# PSU.net
KiCad netlist of a schematic drawn in Altium Designer
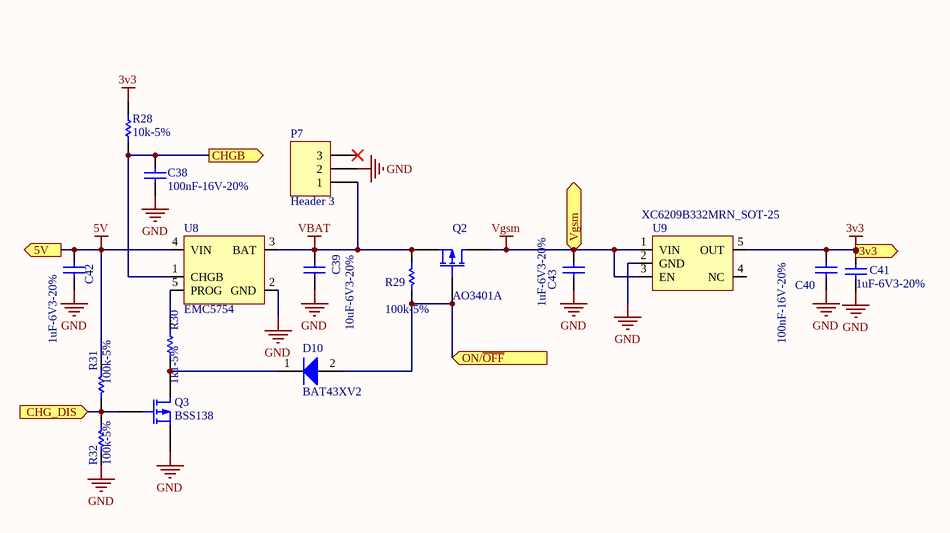
[diagram p0: PSU.SchDoc]

(export (version "E")
  (design (tool "Eeschema 10.0.6"))
  (components
    (comp (ref "C38")
      (value "100nF-16V-20%")
      (footprint "C0402")
      (description "CAP CER 0.1UF 16V Y5V 0402")
      (fields
        (field (name "MANUFACTURER") "Yageo")
        (field (name "DIGI-KEY PART NUMBER") "311-1047-1-ND")
        (field (name "PUBLISHER") "Altium Limited")
      )
      (libsource (lib "Miscellaneous Devices") (part "Cap"))
    )
    (comp (ref "C39")
      (value "10uF-6V3-20%")
      (footprint "C0402")
      (description "CAP CER 10UF 6.3V 20% X5R 0603")
      (fields
        (field (name "MANUFACTURER") "Yageo")
        (field (name "DIGI-KEY PART NUMBER") "311-1448-1-ND")
        (field (name "PUBLISHER") "Altium Limited")
      )
      (libsource (lib "Miscellaneous Devices") (part "Cap"))
    )
    (comp (ref "C40")
      (value "100nF-16V-20%")
      (footprint "C0402")
      (description "CAP CER 0.1UF 16V Y5V 0402")
      (fields
        (field (name "MANUFACTURER") "Yageo")
        (field (name "DIGI-KEY PART NUMBER") "311-1047-1-ND")
        (field (name "PUBLISHER") "Altium Limited")
      )
      (libsource (lib "Miscellaneous Devices") (part "Cap"))
    )
    (comp (ref "C41")
      (value "1uF-6V3-20%")
      (footprint "C0402")
      (description "CAP CER 1UF 6.3V Y5V 0402")
      (fields
        (field (name "MANUFACTURER") "Yageo")
        (field (name "DIGI-KEY PART NUMBER") "311-1377-2-ND")
        (field (name "PUBLISHER") "Altium Limited")
      )
      (libsource (lib "Miscellaneous Devices") (part "Cap"))
    )
    (comp (ref "C42")
      (value "1uF-6V3-20%")
      (footprint "C0402")
      (description "CAP CER 1UF 6.3V Y5V 0402")
      (fields
        (field (name "MANUFACTURER") "Yageo")
        (field (name "DIGI-KEY PART NUMBER") "311-1377-2-ND")
        (field (name "PUBLISHER") "Altium Limited")
      )
      (libsource (lib "Miscellaneous Devices") (part "Cap"))
    )
    (comp (ref "C43")
      (value "1uF-6V3-20%")
      (footprint "C0402")
      (description "CAP CER 1UF 6.3V Y5V 0402")
      (fields
        (field (name "MANUFACTURER") "Yageo")
        (field (name "DIGI-KEY PART NUMBER") "311-1377-2-ND")
        (field (name "PUBLISHER") "Altium Limited")
      )
      (libsource (lib "Miscellaneous Devices") (part "Cap"))
    )
    (comp (ref "D10")
      (value "BAT43XV2")
      (footprint "SOD-523F")
      (description "Diode Type SMD")
      (fields
        (field (name "DIGI-KEY PART NUMBER") "BAT43XV2CT-ND")
        (field (name "MANUFACTURER") "Fairchild Semiconductor")
        (field (name "PUBLISHER") "Altium Limited")
      )
      (libsource (lib "Miscellaneous Devices") (part "Diode"))
    )
    (comp (ref "P7")
      (value "Header 3")
      (footprint "BAT_CON")
      (description "Header, 3-Pin")
      (fields (field (name "PUBLISHER") "Altium Limited"))
      (libsource (lib "Miscellaneous Connectors") (part "Header 3"))
    )
    (comp (ref "Q2")
      (value "AO3401A")
      (footprint "SOT23-3")
      (description "MOSFET P-CH -30V -4.3A SOT23")
      (fields
        (field (name "DIGI-KEY PART NUMBER") "785-1001-1-ND")
        (field (name "MANUFACTURER") "Alpha & Omega Semiconductor Inc")
        (field (name "PUBLISHER") "Altium Limited")
      )
      (libsource (lib "") (part "MOSFET-P_1"))
    )
    (comp (ref "Q3")
      (value "BSS138")
      (footprint "SOT23-3")
      (description "MOSFET N-CH 50V 200MA SOT23-3")
      (fields
        (field (name "DIGI-KEY PART NUMBER") "BSS138-FDICT-ND")
        (field (name "MANUFACTURER") "Diodes Inc")
        (field (name "PUBLISHER") "Altium Limited")
      )
      (libsource (lib "Miscellaneous Devices") (part "MOSFET-P"))
    )
    (comp (ref "R28")
      (value "10k-5%")
      (footprint "R0402")
      (description "RES 10K OHM 1/16W 5% 0402 SMD")
      (fields
        (field (name "DIGI-KEY PART NUMBER") "311-10KJRCT-ND")
        (field (name "MANUFACTURER") "Yageo")
        (field (name "PUBLISHER") "Altium Limited")
      )
      (libsource (lib "Miscellaneous Devices") (part "Res1"))
    )
    (comp (ref "R29")
      (value "100k-5%")
      (footprint "R0402")
      (description "RES 100K OHM 1/16W 5% 0402 SMD")
      (fields
        (field (name "DIGI-KEY PART NUMBER") "311-100KJRCT-ND")
        (field (name "MANUFACTURER") "Yageo")
        (field (name "PUBLISHER") "Altium Limited")
      )
      (libsource (lib "Miscellaneous Devices") (part "Res1"))
    )
    (comp (ref "R30")
      (value "1k1-5%")
      (footprint "R0402")
      (description "RES 1.1K OHM 1/16W 5% 0402 SMD")
      (fields
        (field (name "DIGI-KEY PART NUMBER") "311-1.1KJRCT-ND")
        (field (name "MANUFACTURER") "Yageo")
        (field (name "PUBLISHER") "Altium Limited")
      )
      (libsource (lib "Miscellaneous Devices") (part "Res1"))
    )
    (comp (ref "R31")
      (value "100k-5%")
      (footprint "R0402")
      (description "RES 100K OHM 1/16W 5% 0402 SMD")
      (fields
        (field (name "DIGI-KEY PART NUMBER") "311-100KJRCT-ND")
        (field (name "MANUFACTURER") "Yageo")
        (field (name "PUBLISHER") "Altium Limited")
      )
      (libsource (lib "Miscellaneous Devices") (part "Res1"))
    )
    (comp (ref "R32")
      (value "100k-5%")
      (footprint "R0402")
      (description "RES 100K OHM 1/16W 5% 0402 SMD")
      (fields
        (field (name "DIGI-KEY PART NUMBER") "311-100KJRCT-ND")
        (field (name "MANUFACTURER") "Yageo")
        (field (name "PUBLISHER") "Altium Limited")
      )
      (libsource (lib "Miscellaneous Devices") (part "Res1"))
    )
    (comp (ref "U8") (value "EMC5754") (footprint "SOT23-5") (libsource (lib "Lib") (part "EMC5754")))
    (comp (ref "U9")
      (value "XC6209B332MRN_SOT-25")
      (footprint "SOT23-5")
      (fields (field (name "MANUFACTURER") "Tyrone"))
      (libsource (lib "Schlib1") (part "XC6209B332MRN_SOT-25"))
    )
  )
  (nets
    (net (code "2") (name "/CHGB") (class "Default")
      (node (ref "C38") (pin "2") (pinfunction "2_2") (pintype "passive"))
      (node (ref "R28") (pin "1") (pinfunction "1_1") (pintype "passive"))
      (node (ref "U8") (pin "1") (pinfunction "CHGB_1") (pintype "passive"))
    )
    (net (code "3") (name "/CHG_DIS") (class "Default")
      (node (ref "Q3") (pin "1") (pinfunction "G_1") (pintype "passive"))
      (node (ref "R31") (pin "1") (pinfunction "1_1") (pintype "passive"))
      (node (ref "R32") (pin "2") (pinfunction "2_2") (pintype "passive"))
    )
    (net (code "4") (name "/ON{slash}~{OFF}") (class "Default")
      (node (ref "D10") (pin "2") (pinfunction "A_2") (pintype "passive"))
      (node (ref "Q2") (pin "1") (pinfunction "G_1") (pintype "passive"))
      (node (ref "R29") (pin "1") (pinfunction "1_1") (pintype "passive"))
    )
    (net (code "5") (name "3v3") (class "Default")
      (node (ref "C40") (pin "2") (pinfunction "2_2") (pintype "passive"))
      (node (ref "C41") (pin "1") (pinfunction "1_1") (pintype "passive"))
      (node (ref "R28") (pin "2") (pinfunction "2_2") (pintype "passive"))
      (node (ref "U9") (pin "5") (pinfunction "OUT_5") (pintype "passive"))
    )
    (net (code "6") (name "5V") (class "Default")
      (node (ref "C42") (pin "2") (pinfunction "2_2") (pintype "passive"))
      (node (ref "R31") (pin "2") (pinfunction "2_2") (pintype "passive"))
      (node (ref "U8") (pin "4") (pinfunction "VIN_4") (pintype "passive"))
    )
    (net (code "7") (name "GND") (class "Default")
      (node (ref "C38") (pin "1") (pinfunction "1_1") (pintype "passive"))
      (node (ref "C39") (pin "1") (pinfunction "1_1") (pintype "passive"))
      (node (ref "C40") (pin "1") (pinfunction "1_1") (pintype "passive"))
      (node (ref "C41") (pin "2") (pinfunction "2_2") (pintype "passive"))
      (node (ref "C42") (pin "1") (pinfunction "1_1") (pintype "passive"))
      (node (ref "C43") (pin "2") (pinfunction "2_2") (pintype "passive"))
      (node (ref "P7") (pin "2") (pinfunction "2_2") (pintype "passive"))
      (node (ref "Q3") (pin "2") (pinfunction "S_2") (pintype "passive"))
      (node (ref "R32") (pin "1") (pinfunction "1_1") (pintype "passive"))
      (node (ref "U8") (pin "2") (pinfunction "GND_2") (pintype "passive"))
      (node (ref "U9") (pin "2") (pinfunction "GND_2") (pintype "passive"))
    )
    (net (code "8") (name "Net-(D10-K)") (class "Default")
      (node (ref "D10") (pin "1") (pinfunction "K_1") (pintype "passive"))
      (node (ref "Q3") (pin "3") (pinfunction "D_3") (pintype "passive"))
      (node (ref "R30") (pin "2") (pinfunction "2_2") (pintype "passive"))
    )
    (net (code "9") (name "Net-(U8-PROG)") (class "Default")
      (node (ref "R30") (pin "1") (pinfunction "1_1") (pintype "passive"))
      (node (ref "U8") (pin "5") (pinfunction "PROG_5") (pintype "passive"))
    )
    (net (code "10") (name "VBAT") (class "Default")
      (node (ref "C39") (pin "2") (pinfunction "2_2") (pintype "passive"))
      (node (ref "P7") (pin "1") (pinfunction "1_1") (pintype "passive"))
      (node (ref "Q2") (pin "2") (pinfunction "S_2") (pintype "passive"))
      (node (ref "R29") (pin "2") (pinfunction "2_2") (pintype "passive"))
      (node (ref "U8") (pin "3") (pinfunction "BAT_3") (pintype "passive"))
    )
    (net (code "11") (name "Vgsm") (class "Default")
      (node (ref "C43") (pin "1") (pinfunction "1_1") (pintype "passive"))
      (node (ref "Q2") (pin "3") (pinfunction "D_3") (pintype "passive"))
      (node (ref "U9") (pin "1") (pinfunction "VIN_1") (pintype "passive"))
      (node (ref "U9") (pin "3") (pinfunction "EN_3") (pintype "passive"))
    )
    (net (code "12") (name "unconnected-(P7-Pad3)") (class "Default")
      (node (ref "P7") (pin "3") (pinfunction "3_3") (pintype "passive+no_connect"))
    )
    (net (code "13") (name "unconnected-(U9-NC-Pad4)") (class "Default")
      (node (ref "U9") (pin "4") (pinfunction "NC_4") (pintype "passive"))
    )
  )
)
